# air_flow.net
KiCad netlist of a schematic drawn in EAGLE
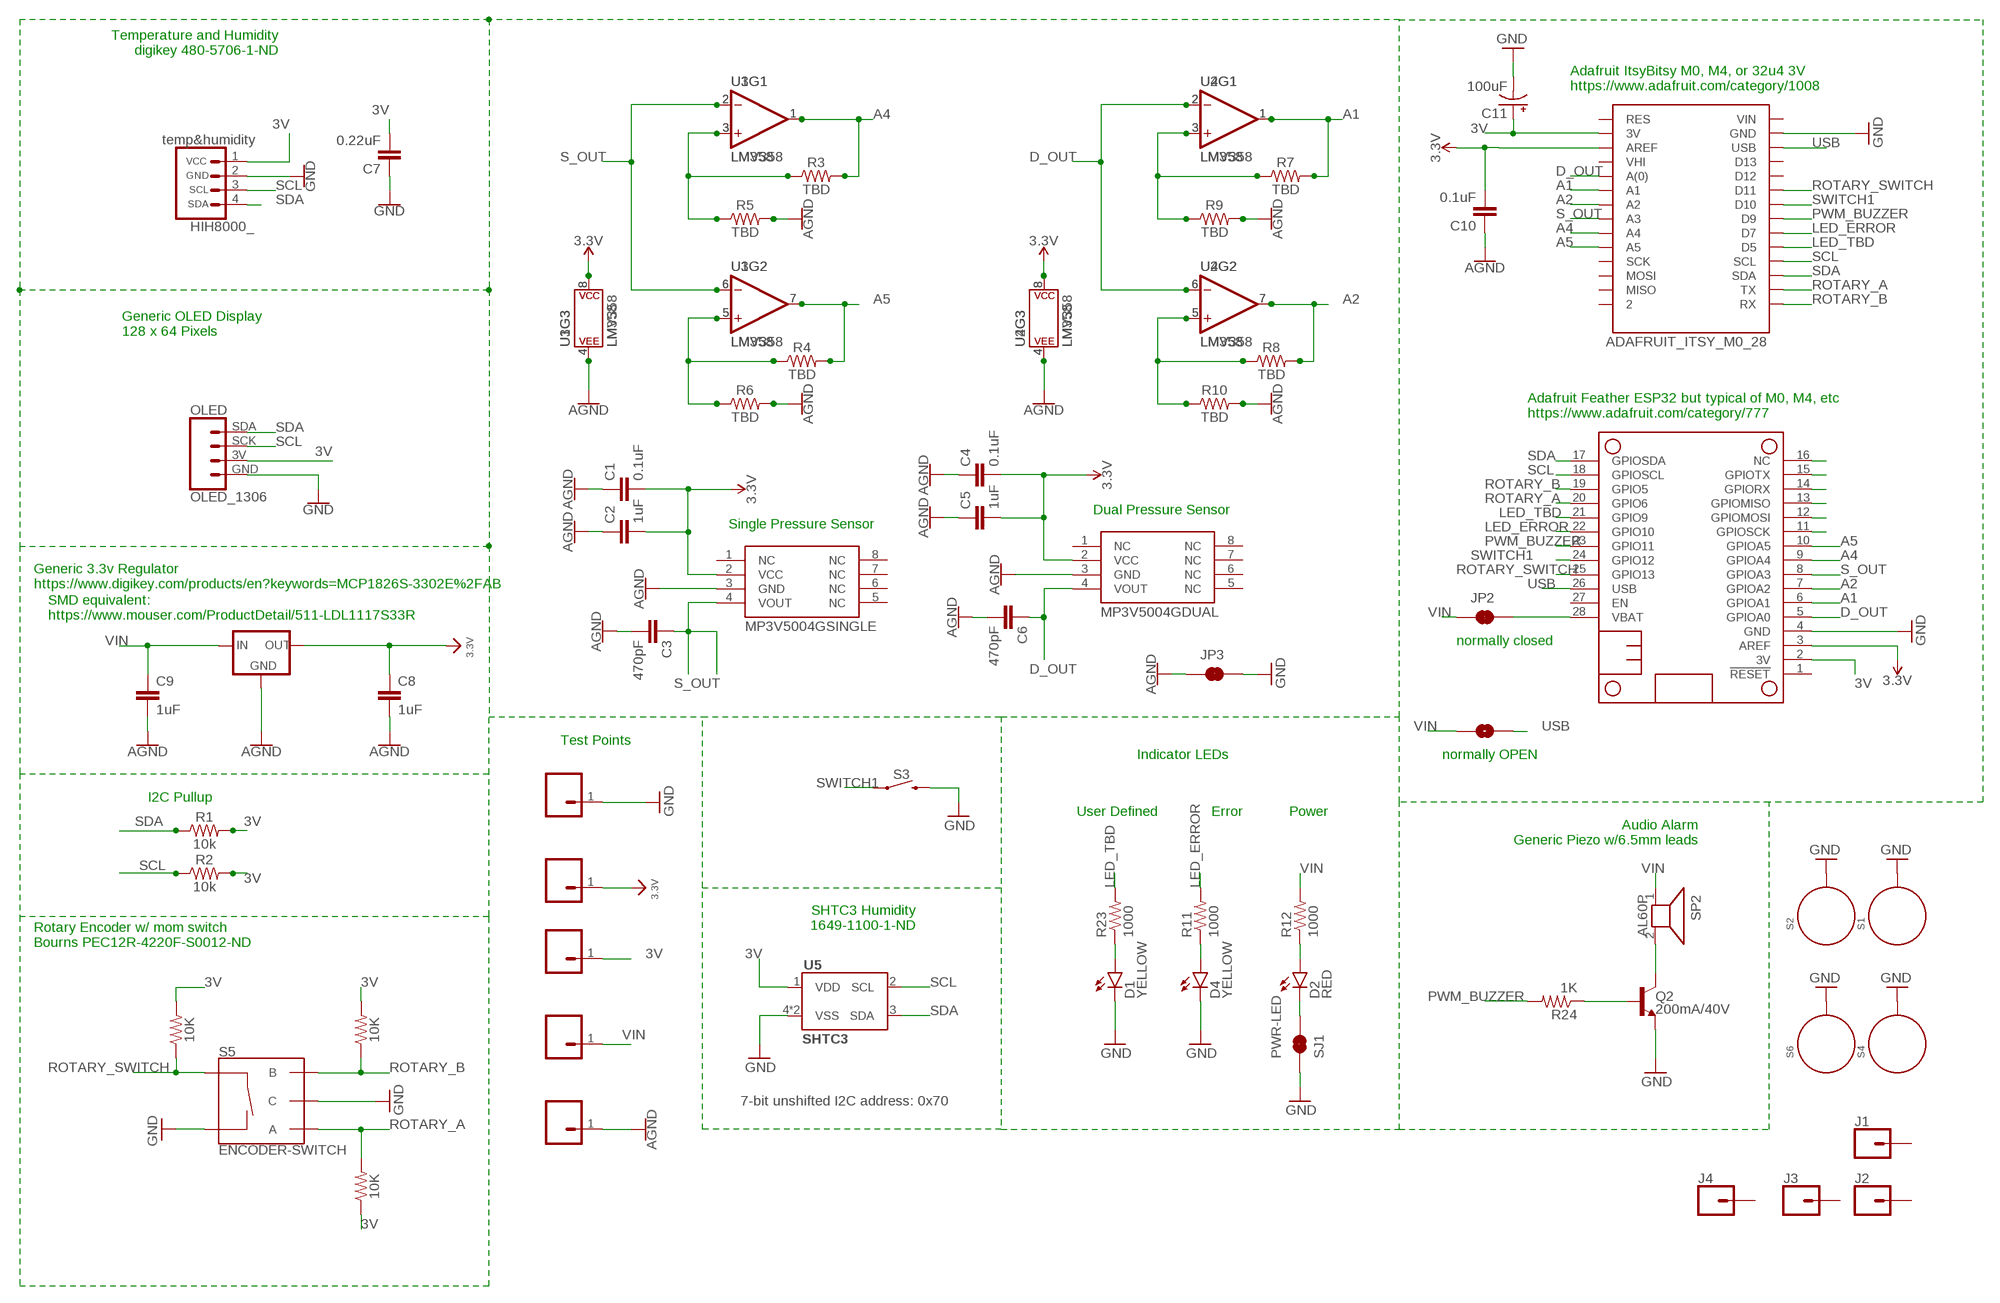
[diagram p0: schematic, sheet 1]

(export (version "E")
  (design (tool "Eeschema 10.0.6"))
  (components
    (comp (ref "3V_REGULATOR")
      (value "LDL1117_5V_REG")
      (footprint "eagle-import:SOT223")
      (libsource (lib "eagle-import") (part "LDL1117_5V_REG"))
    )
    (comp (ref "C1")
      (value "0.1uF")
      (footprint "eagle-import:CAP-PTH-SMALL-KIT")
      (libsource (lib "eagle-import") (part "0.1UF-KIT-EZ-50V-20%"))
    )
    (comp (ref "C2")
      (value "1uF")
      (footprint "eagle-import:CAP-PTH-SMALL-KIT")
      (libsource (lib "eagle-import") (part "0.1UF-KIT-EZ-50V-20%"))
    )
    (comp (ref "C3")
      (value "470pF")
      (footprint "eagle-import:CAP-PTH-SMALL-KIT")
      (libsource (lib "eagle-import") (part "0.1UF-KIT-EZ-50V-20%"))
    )
    (comp (ref "C4")
      (value "0.1uF")
      (footprint "eagle-import:CAP-PTH-SMALL-KIT")
      (libsource (lib "eagle-import") (part "0.1UF-KIT-EZ-50V-20%"))
    )
    (comp (ref "C5")
      (value "1uF")
      (footprint "eagle-import:CAP-PTH-SMALL-KIT")
      (libsource (lib "eagle-import") (part "0.1UF-KIT-EZ-50V-20%"))
    )
    (comp (ref "C6")
      (value "470pF")
      (footprint "eagle-import:CAP-PTH-SMALL-KIT")
      (libsource (lib "eagle-import") (part "0.1UF-KIT-EZ-50V-20%"))
    )
    (comp (ref "C7")
      (value "0.22uF")
      (footprint "eagle-import:CAP-PTH-SMALL-KIT")
      (libsource (lib "eagle-import") (part "0.1UF-KIT-EZ-50V-20%"))
    )
    (comp (ref "C8")
      (value "1uF")
      (footprint "eagle-import:CAP-PTH-SMALL-KIT")
      (libsource (lib "eagle-import") (part "0.1UF-KIT-EZ-50V-20%"))
    )
    (comp (ref "C9")
      (value "1uF")
      (footprint "eagle-import:CAP-PTH-SMALL-KIT")
      (libsource (lib "eagle-import") (part "0.1UF-KIT-EZ-50V-20%"))
    )
    (comp (ref "C10")
      (value "0.1uF")
      (footprint "eagle-import:CAP-PTH-SMALL-KIT")
      (libsource (lib "eagle-import") (part "0.1UF-KIT-EZ-50V-20%"))
    )
    (comp (ref "C11")
      (value "100uF")
      (footprint "eagle-import:CPOL-RADIAL-2.5MM-6.5MM")
      (libsource (lib "eagle-import") (part "100UF-POLAR-RADIAL-2.5MM-25V-20%"))
    )
    (comp (ref "D1")
      (value "YELLOW")
      (footprint "eagle-import:LED-1206")
      (libsource (lib "eagle-import") (part "LED-YELLOWLARGE"))
    )
    (comp (ref "D2")
      (value "RED")
      (footprint "eagle-import:LED-1206")
      (libsource (lib "eagle-import") (part "LED-RED1206"))
    )
    (comp (ref "D4")
      (value "YELLOW")
      (footprint "eagle-import:LED-1206")
      (libsource (lib "eagle-import") (part "LED-YELLOWLARGE"))
    )
    (comp (ref "J1")
      (value "CONN_01")
      (footprint "eagle-import:1X01")
      (libsource (lib "eagle-import") (part "CONN_01"))
    )
    (comp (ref "J2")
      (value "CONN_01")
      (footprint "eagle-import:1X01")
      (libsource (lib "eagle-import") (part "CONN_01"))
    )
    (comp (ref "J3")
      (value "CONN_01")
      (footprint "eagle-import:1X01")
      (libsource (lib "eagle-import") (part "CONN_01"))
    )
    (comp (ref "J4")
      (value "CONN_01")
      (footprint "eagle-import:1X01")
      (libsource (lib "eagle-import") (part "CONN_01"))
    )
    (comp (ref "JP1")
      (value "JUMPER-SMT_2_NO_NO-SILK")
      (footprint "eagle-import:SMT-JUMPER_2_NO_NO-SILK")
      (libsource (lib "eagle-import") (part "JUMPER-SMT_2_NO_NO-SILK"))
    )
    (comp (ref "JP2")
      (value "JUMPER-SMT_2_NC_TRACE_SILK")
      (footprint "eagle-import:SMT-JUMPER_2_NC_TRACE_SILK")
      (libsource (lib "eagle-import") (part "JUMPER-SMT_2_NC_TRACE_SILK"))
    )
    (comp (ref "JP3")
      (value "JUMPER-SMT_2_NC_TRACE_SILK")
      (footprint "eagle-import:SMT-JUMPER_2_NC_TRACE_SILK")
      (libsource (lib "eagle-import") (part "JUMPER-SMT_2_NC_TRACE_SILK"))
    )
    (comp (ref "MS2")
      (value "FEATHERWING_NODIM")
      (footprint "eagle-import:FEATHERWING_DIM")
      (libsource (lib "eagle-import") (part "FEATHERWING_NODIM"))
    )
    (comp (ref "Q2")
      (value "200mA/40V")
      (footprint "eagle-import:TO-92")
      (libsource (lib "eagle-import") (part "TRANS_NPN-2N3904"))
    )
    (comp (ref "R1")
      (value "10k")
      (footprint "eagle-import:AXIAL-0.3")
      (libsource (lib "eagle-import") (part "10KOHM-HORIZ-1/4W-5%"))
    )
    (comp (ref "R2")
      (value "10k")
      (footprint "eagle-import:AXIAL-0.3")
      (libsource (lib "eagle-import") (part "10KOHM-HORIZ-1/4W-5%"))
    )
    (comp (ref "R3")
      (value "TBD")
      (footprint "eagle-import:AXIAL-0.3")
      (libsource (lib "eagle-import") (part "10KOHM-HORIZ-1/4W-5%"))
    )
    (comp (ref "R4")
      (value "TBD")
      (footprint "eagle-import:AXIAL-0.3")
      (libsource (lib "eagle-import") (part "10KOHM-HORIZ-1/4W-5%"))
    )
    (comp (ref "R5")
      (value "TBD")
      (footprint "eagle-import:AXIAL-0.3")
      (libsource (lib "eagle-import") (part "10KOHM-HORIZ-1/4W-5%"))
    )
    (comp (ref "R6")
      (value "TBD")
      (footprint "eagle-import:AXIAL-0.3")
      (libsource (lib "eagle-import") (part "10KOHM-HORIZ-1/4W-5%"))
    )
    (comp (ref "R7")
      (value "TBD")
      (footprint "eagle-import:AXIAL-0.3")
      (libsource (lib "eagle-import") (part "10KOHM-HORIZ-1/4W-5%"))
    )
    (comp (ref "R8")
      (value "TBD")
      (footprint "eagle-import:AXIAL-0.3")
      (libsource (lib "eagle-import") (part "10KOHM-HORIZ-1/4W-5%"))
    )
    (comp (ref "R9")
      (value "TBD")
      (footprint "eagle-import:AXIAL-0.3")
      (libsource (lib "eagle-import") (part "10KOHM-HORIZ-1/4W-5%"))
    )
    (comp (ref "R10")
      (value "TBD")
      (footprint "eagle-import:AXIAL-0.3")
      (libsource (lib "eagle-import") (part "10KOHM-HORIZ-1/4W-5%"))
    )
    (comp (ref "R11")
      (value "1000")
      (footprint "eagle-import:0805")
      (libsource (lib "eagle-import") (part "RESISTOR0805-RES"))
    )
    (comp (ref "R12")
      (value "1000")
      (footprint "eagle-import:0805")
      (libsource (lib "eagle-import") (part "RESISTOR0805-RES"))
    )
    (comp (ref "R13")
      (value "0.3")
      (footprint "eagle-import:0805")
      (libsource (lib "eagle-import") (part "0.3OHM-0805-1/8W-1%"))
    )
    (comp (ref "R14")
      (value "0.3")
      (footprint "eagle-import:0805")
      (libsource (lib "eagle-import") (part "0.3OHM-0805-1/8W-1%"))
    )
    (comp (ref "R15")
      (value "0.3")
      (footprint "eagle-import:0805")
      (libsource (lib "eagle-import") (part "0.3OHM-0805-1/8W-1%"))
    )
    (comp (ref "R16")
      (value "0.3")
      (footprint "eagle-import:0805")
      (libsource (lib "eagle-import") (part "0.3OHM-0805-1/8W-1%"))
    )
    (comp (ref "R17")
      (value "0.3")
      (footprint "eagle-import:0805")
      (libsource (lib "eagle-import") (part "0.3OHM-0805-1/8W-1%"))
    )
    (comp (ref "R18")
      (value "0.3")
      (footprint "eagle-import:0805")
      (libsource (lib "eagle-import") (part "0.3OHM-0805-1/8W-1%"))
    )
    (comp (ref "R19")
      (value "0.3")
      (footprint "eagle-import:0805")
      (libsource (lib "eagle-import") (part "0.3OHM-0805-1/8W-1%"))
    )
    (comp (ref "R20")
      (value "0.3")
      (footprint "eagle-import:0805")
      (libsource (lib "eagle-import") (part "0.3OHM-0805-1/8W-1%"))
    )
    (comp (ref "R21")
      (value "0.3")
      (footprint "eagle-import:0805")
      (libsource (lib "eagle-import") (part "0.3OHM-0805-1/8W-1%"))
    )
    (comp (ref "R22")
      (value "0.3")
      (footprint "eagle-import:0805")
      (libsource (lib "eagle-import") (part "0.3OHM-0805-1/8W-1%"))
    )
    (comp (ref "R23")
      (value "1000")
      (footprint "eagle-import:0805")
      (libsource (lib "eagle-import") (part "RESISTOR0805-RES"))
    )
    (comp (ref "R24")
      (value "1K")
      (footprint "eagle-import:0805")
      (libsource (lib "eagle-import") (part "RESISTOR0805-RES"))
    )
    (comp (ref "R26")
      (value "10K")
      (footprint "eagle-import:0805")
      (libsource (lib "eagle-import") (part "0.3OHM-0805-1/8W-1%"))
    )
    (comp (ref "R27")
      (value "10K")
      (footprint "eagle-import:0805")
      (libsource (lib "eagle-import") (part "0.3OHM-0805-1/8W-1%"))
    )
    (comp (ref "R28")
      (value "10K")
      (footprint "eagle-import:0805")
      (libsource (lib "eagle-import") (part "0.3OHM-0805-1/8W-1%"))
    )
    (comp (ref "S1")
      (value "STANDOFF_ELECTRICAL5-32")
      (footprint "eagle-import:STANDOFF_ELECTRICAL_5_32")
      (libsource (lib "eagle-import") (part "STANDOFF_ELECTRICAL5-32"))
    )
    (comp (ref "S2")
      (value "STANDOFF_ELECTRICAL5-32")
      (footprint "eagle-import:STANDOFF_ELECTRICAL_5_32")
      (libsource (lib "eagle-import") (part "STANDOFF_ELECTRICAL5-32"))
    )
    (comp (ref "S3")
      (value "MOMENTARY-SWITCH-SPST-PTH-6.0MM-KIT")
      (footprint "eagle-import:TACTILE_SWITCH_PTH_6.0MM_KIT")
      (libsource (lib "eagle-import") (part "MOMENTARY-SWITCH-SPST-PTH-6.0MM-KIT"))
    )
    (comp (ref "S4")
      (value "STANDOFF_ELECTRICAL5-32")
      (footprint "eagle-import:STANDOFF_ELECTRICAL_5_32")
      (libsource (lib "eagle-import") (part "STANDOFF_ELECTRICAL5-32"))
    )
    (comp (ref "S5")
      (value "ENCODER-SWITCH")
      (footprint "eagle-import:ROTARY_ENC_PLAIN")
      (libsource (lib "eagle-import") (part "ENCODER-SWITCH"))
    )
    (comp (ref "S6")
      (value "STANDOFF_ELECTRICAL5-32")
      (footprint "eagle-import:STANDOFF_ELECTRICAL_5_32")
      (libsource (lib "eagle-import") (part "STANDOFF_ELECTRICAL5-32"))
    )
    (comp (ref "SJ1")
      (value "PWR-LED")
      (footprint "eagle-import:PAD-JUMPER-2-NC_BY_TRACE_NO_SILK")
      (libsource (lib "eagle-import") (part "JUMPER-PAD-2-NC_BY_TRACENO_SILK"))
    )
    (comp (ref "SP2")
      (value "AL60P")
      (footprint "eagle-import:AL60P")
      (libsource (lib "eagle-import") (part "AL60P"))
    )
    (comp (ref "U$1")
      (value "OLED_1306")
      (footprint "eagle-import:OLED_1306")
      (libsource (lib "eagle-import") (part "OLED_1306"))
    )
    (comp (ref "U$2")
      (value "MP3V5004GSINGLE")
      (footprint "eagle-import:MP3V5004GP")
      (libsource (lib "eagle-import") (part "MP3V5004GSINGLE"))
    )
    (comp (ref "U$3")
      (value "MP3V5004GDUAL")
      (footprint "eagle-import:MP3V5004DP")
      (libsource (lib "eagle-import") (part "MP3V5004GDUAL"))
    )
    (comp (ref "U$4")
      (value "HIH8000_")
      (footprint "eagle-import:HIH8120_TH")
      (libsource (lib "eagle-import") (part "HIH8000_"))
    )
    (comp (ref "U$20")
      (value "CONN_0138MILL")
      (footprint "eagle-import:1X01-40MILL")
      (libsource (lib "eagle-import") (part "CONN_0138MILL"))
    )
    (comp (ref "U$26")
      (value "CONN_0138MILL")
      (footprint "eagle-import:1X01-40MILL")
      (libsource (lib "eagle-import") (part "CONN_0138MILL"))
    )
    (comp (ref "U$31")
      (value "CONN_0138MILL")
      (footprint "eagle-import:1X01-40MILL")
      (libsource (lib "eagle-import") (part "CONN_0138MILL"))
    )
    (comp (ref "U$39")
      (value "CONN_0138MILL")
      (footprint "eagle-import:1X01-40MILL")
      (libsource (lib "eagle-import") (part "CONN_0138MILL"))
    )
    (comp (ref "U$40")
      (value "CONN_0138MILL")
      (footprint "eagle-import:1X01-40MILL")
      (libsource (lib "eagle-import") (part "CONN_0138MILL"))
    )
    (comp (ref "U$45")
      (value "ADAFRUIT_ITSY_M0_28")
      (footprint "eagle-import:ADAFRUIT_ITS_MO_28")
      (libsource (lib "eagle-import") (part "ADAFRUIT_ITSY_M0_28"))
    )
    (comp (ref "U1")
      (value "LM358")
      (footprint "eagle-import:DIP08")
      (libsource (lib "eagle-import") (part "LM358"))
    )
    (comp (ref "U2")
      (value "LM358")
      (footprint "eagle-import:DIP08")
      (libsource (lib "eagle-import") (part "LM358"))
    )
    (comp (ref "U3")
      (value "LMV358")
      (footprint "eagle-import:SO08")
      (libsource (lib "eagle-import") (part "LMV358SOIC"))
    )
    (comp (ref "U4")
      (value "LMV358")
      (footprint "eagle-import:SO08")
      (libsource (lib "eagle-import") (part "LMV358SOIC"))
    )
    (comp (ref "U5")
      (value "SHTC3")
      (footprint "eagle-import:SHTC3")
      (libsource (lib "eagle-import") (part "SHTC3"))
    )
  )
  (nets
    (net (code "1") (name "/3V") (class "Default")
      (node (ref "C11") (pin "1") (pinfunction "+_1") (pintype "passive"))
      (node (ref "C7") (pin "2") (pinfunction "2_2") (pintype "passive"))
      (node (ref "MS2") (pin "2") (pinfunction "3V_2") (pintype "power_in"))
      (node (ref "R1") (pin "P$2") (pinfunction "2_P$2") (pintype "passive"))
      (node (ref "R2") (pin "P$2") (pinfunction "2_P$2") (pintype "passive"))
      (node (ref "R21") (pin "2") (pinfunction "2_2") (pintype "passive"))
      (node (ref "R22") (pin "2") (pinfunction "2_2") (pintype "passive"))
      (node (ref "R26") (pin "2") (pinfunction "2_2") (pintype "passive"))
      (node (ref "R27") (pin "1") (pinfunction "1_1") (pintype "passive"))
      (node (ref "R28") (pin "2") (pinfunction "2_2") (pintype "passive"))
      (node (ref "U$1") (pin "3V") (pinfunction "VCC_3V") (pintype "power_in"))
      (node (ref "U$20") (pin "1") (pinfunction "1_1") (pintype "passive"))
      (node (ref "U$4") (pin "1") (pinfunction "VCC_1") (pintype "passive"))
      (node (ref "U$45") (pin "3V") (pinfunction "3V_3V") (pintype "bidirectional"))
      (node (ref "U5") (pin "1") (pinfunction "VDD_1") (pintype "bidirectional"))
    )
    (net (code "2") (name "/A1") (class "Default")
      (node (ref "MS2") (pin "6") (pinfunction "GPIOA1_6") (pintype "bidirectional"))
      (node (ref "R17") (pin "2") (pinfunction "2_2") (pintype "passive"))
      (node (ref "R7") (pin "P$2") (pinfunction "2_P$2") (pintype "passive"))
      (node (ref "U$45") (pin "A1") (pinfunction "A1_A1") (pintype "bidirectional"))
      (node (ref "U2") (pin "1") (pinfunction "OUT_1") (pintype "output"))
      (node (ref "U4") (pin "1") (pinfunction "OUT_1") (pintype "output"))
    )
    (net (code "3") (name "/A2") (class "Default")
      (node (ref "MS2") (pin "7") (pinfunction "GPIOA2_7") (pintype "bidirectional"))
      (node (ref "R19") (pin "2") (pinfunction "2_2") (pintype "passive"))
      (node (ref "R8") (pin "P$2") (pinfunction "2_P$2") (pintype "passive"))
      (node (ref "U$45") (pin "A2") (pinfunction "A2_A2") (pintype "bidirectional"))
      (node (ref "U2") (pin "7") (pinfunction "OUT_7") (pintype "output"))
      (node (ref "U4") (pin "7") (pinfunction "OUT_7") (pintype "output"))
    )
    (net (code "4") (name "/A4") (class "Default")
      (node (ref "MS2") (pin "9") (pinfunction "GPIOA4_9") (pintype "bidirectional"))
      (node (ref "R16") (pin "2") (pinfunction "2_2") (pintype "passive"))
      (node (ref "R3") (pin "P$2") (pinfunction "2_P$2") (pintype "passive"))
      (node (ref "U$45") (pin "A4") (pinfunction "A4_A4") (pintype "bidirectional"))
      (node (ref "U1") (pin "1") (pinfunction "OUT_1") (pintype "output"))
      (node (ref "U3") (pin "1") (pinfunction "OUT_1") (pintype "output"))
    )
    (net (code "5") (name "/A5") (class "Default")
      (node (ref "MS2") (pin "10") (pinfunction "GPIOA5_10") (pintype "bidirectional"))
      (node (ref "R14") (pin "2") (pinfunction "2_2") (pintype "passive"))
      (node (ref "R4") (pin "P$2") (pinfunction "2_P$2") (pintype "passive"))
      (node (ref "U$45") (pin "A5") (pinfunction "A5_A5") (pintype "bidirectional"))
      (node (ref "U1") (pin "7") (pinfunction "OUT_7") (pintype "output"))
      (node (ref "U3") (pin "7") (pinfunction "OUT_7") (pintype "output"))
    )
    (net (code "6") (name "/D_OUT") (class "Default")
      (node (ref "C6") (pin "1") (pinfunction "1_1") (pintype "passive"))
      (node (ref "MS2") (pin "5") (pinfunction "GPIOA0_5") (pintype "bidirectional"))
      (node (ref "U$3") (pin "4") (pinfunction "VOUT_4") (pintype "bidirectional"))
      (node (ref "U$45") (pin "A0") (pinfunction "A(0)_A0") (pintype "bidirectional"))
      (node (ref "U2") (pin "2") (pinfunction "-IN_2") (pintype "input"))
      (node (ref "U2") (pin "6") (pinfunction "-IN_6") (pintype "input"))
      (node (ref "U4") (pin "2") (pinfunction "-IN_2") (pintype "input"))
      (node (ref "U4") (pin "6") (pinfunction "-IN_6") (pintype "input"))
    )
    (net (code "7") (name "/LED_ERROR") (class "Default")
      (node (ref "MS2") (pin "22") (pinfunction "GPIO10_22") (pintype "bidirectional"))
      (node (ref "R11") (pin "2") (pinfunction "2_2") (pintype "passive"))
      (node (ref "U$45") (pin "D7") (pinfunction "D7_D7") (pintype "bidirectional"))
    )
    (net (code "8") (name "/LED_TBD") (class "Default")
      (node (ref "MS2") (pin "21") (pinfunction "GPIO9_21") (pintype "bidirectional"))
      (node (ref "R23") (pin "2") (pinfunction "2_2") (pintype "passive"))
      (node (ref "U$45") (pin "D5") (pinfunction "D5_D5") (pintype "bidirectional"))
    )
    (net (code "9") (name "/PWM_BUZZER") (class "Default")
      (node (ref "MS2") (pin "23") (pinfunction "GPIO11_23") (pintype "bidirectional"))
      (node (ref "R24") (pin "2") (pinfunction "2_2") (pintype "passive"))
      (node (ref "U$45") (pin "D9") (pinfunction "D9_D9") (pintype "bidirectional"))
    )
    (net (code "10") (name "/ROTARY_A") (class "Default")
      (node (ref "MS2") (pin "20") (pinfunction "GPIO6_20") (pintype "bidirectional"))
      (node (ref "R27") (pin "2") (pinfunction "2_2") (pintype "passive"))
      (node (ref "S5") (pin "A") (pinfunction "A_A") (pintype "bidirectional"))
      (node (ref "U$45") (pin "TX") (pinfunction "TX_TX") (pintype "bidirectional"))
    )
    (net (code "11") (name "/ROTARY_B") (class "Default")
      (node (ref "MS2") (pin "19") (pinfunction "GPIO5_19") (pintype "bidirectional"))
      (node (ref "R26") (pin "1") (pinfunction "1_1") (pintype "passive"))
      (node (ref "S5") (pin "B") (pinfunction "B_B") (pintype "bidirectional"))
      (node (ref "U$45") (pin "RX") (pinfunction "RX_RX") (pintype "bidirectional"))
    )
    (net (code "12") (name "/ROTARY_SWITCH") (class "Default")
      (node (ref "MS2") (pin "25") (pinfunction "GPIO13_25") (pintype "bidirectional"))
      (node (ref "R28") (pin "1") (pinfunction "1_1") (pintype "passive"))
      (node (ref "S5") (pin "SW+") (pinfunction "SW+_SW+") (pintype "bidirectional"))
      (node (ref "U$45") (pin "D11") (pinfunction "D11_D11") (pintype "bidirectional"))
    )
    (net (code "13") (name "/SCL") (class "Default")
      (node (ref "MS2") (pin "18") (pinfunction "GPIOSCL_18") (pintype "bidirectional"))
      (node (ref "R2") (pin "P$1") (pinfunction "1_P$1") (pintype "passive"))
      (node (ref "R22") (pin "1") (pinfunction "1_1") (pintype "passive"))
      (node (ref "U$1") (pin "SCK") (pinfunction "SCK_SCK") (pintype "passive"))
      (node (ref "U$4") (pin "3") (pinfunction "SCL_3") (pintype "power_in"))
      (node (ref "U$45") (pin "SCL") (pinfunction "SCL_SCL") (pintype "bidirectional"))
      (node (ref "U5") (pin "2") (pinfunction "SCL_2") (pintype "bidirectional"))
    )
    (net (code "14") (name "/SDA") (class "Default")
      (node (ref "MS2") (pin "17") (pinfunction "GPIOSDA_17") (pintype "bidirectional"))
      (node (ref "R1") (pin "P$1") (pinfunction "1_P$1") (pintype "passive"))
      (node (ref "R21") (pin "1") (pinfunction "1_1") (pintype "passive"))
      (node (ref "U$1") (pin "SDA") (pinfunction "SDA_SDA") (pintype "passive"))
      (node (ref "U$4") (pin "4") (pinfunction "SDA_4") (pintype "passive"))
      (node (ref "U$45") (pin "SDA") (pinfunction "SDA_SDA") (pintype "bidirectional"))
      (node (ref "U5") (pin "3") (pinfunction "SDA_3") (pintype "bidirectional"))
    )
    (net (code "15") (name "/SWITCH1") (class "Default")
      (node (ref "MS2") (pin "24") (pinfunction "GPIO12_24") (pintype "bidirectional"))
      (node (ref "S3") (pin "1") (pinfunction "1_1") (pintype "passive"))
      (node (ref "U$45") (pin "D10") (pinfunction "D10_D10") (pintype "bidirectional"))
    )
    (net (code "16") (name "/S_OUT") (class "Default")
      (node (ref "C3") (pin "1") (pinfunction "1_1") (pintype "passive"))
      (node (ref "MS2") (pin "8") (pinfunction "GPIOA3_8") (pintype "bidirectional"))
      (node (ref "U$2") (pin "4") (pinfunction "VOUT_4") (pintype "bidirectional"))
      (node (ref "U$45") (pin "A3") (pinfunction "A3_A3") (pintype "bidirectional"))
      (node (ref "U1") (pin "2") (pinfunction "-IN_2") (pintype "input"))
      (node (ref "U1") (pin "6") (pinfunction "-IN_6") (pintype "input"))
      (node (ref "U3") (pin "2") (pinfunction "-IN_2") (pintype "input"))
      (node (ref "U3") (pin "6") (pinfunction "-IN_6") (pintype "input"))
    )
    (net (code "17") (name "/USB") (class "Default")
      (node (ref "JP1") (pin "2") (pinfunction "2_2") (pintype "passive"))
      (node (ref "MS2") (pin "26") (pinfunction "USB_26") (pintype "power_in"))
      (node (ref "U$45") (pin "USB") (pinfunction "USB_USB") (pintype "bidirectional"))
    )
    (net (code "18") (name "/VIN") (class "Default")
      (node (ref "3V_REGULATOR") (pin "3") (pinfunction "IN_3") (pintype "input"))
      (node (ref "C9") (pin "1") (pinfunction "1_1") (pintype "passive"))
      (node (ref "JP1") (pin "1") (pinfunction "1_1") (pintype "passive"))
      (node (ref "JP2") (pin "1") (pinfunction "1_1") (pintype "passive"))
      (node (ref "R12") (pin "2") (pinfunction "2_2") (pintype "passive"))
      (node (ref "SP2") (pin "1") (pinfunction "1_1") (pintype "passive"))
      (node (ref "U$40") (pin "1") (pinfunction "1_1") (pintype "passive"))
    )
    (net (code "19") (name "3.3V") (class "Default")
      (node (ref "3V_REGULATOR") (pin "2") (pinfunction "OUT_2") (pintype "passive"))
      (node (ref "3V_REGULATOR") (pin "4") (pinfunction "OUT_4") (pintype "passive"))
      (node (ref "C1") (pin "2") (pinfunction "2_2") (pintype "passive"))
      (node (ref "C10") (pin "2") (pinfunction "2_2") (pintype "passive"))
      (node (ref "C2") (pin "2") (pinfunction "2_2") (pintype "passive"))
      (node (ref "C4") (pin "2") (pinfunction "2_2") (pintype "passive"))
      (node (ref "C5") (pin "2") (pinfunction "2_2") (pintype "passive"))
      (node (ref "C8") (pin "1") (pinfunction "1_1") (pintype "passive"))
      (node (ref "MS2") (pin "3") (pinfunction "AREF_3") (pintype "passive"))
      (node (ref "U$2") (pin "2") (pinfunction "VCC_2") (pintype "bidirectional"))
      (node (ref "U$3") (pin "2") (pinfunction "VCC_2") (pintype "bidirectional"))
      (node (ref "U$39") (pin "1") (pinfunction "1_1") (pintype "passive"))
      (node (ref "U$45") (pin "AREF") (pinfunction "AREF_AREF") (pintype "bidirectional"))
      (node (ref "U1") (pin "8") (pinfunction "P$V+_8") (pintype "bidirectional"))
      (node (ref "U2") (pin "8") (pinfunction "P$V+_8") (pintype "bidirectional"))
      (node (ref "U3") (pin "8") (pinfunction "P$V+_8") (pintype "bidirectional"))
      (node (ref "U4") (pin "8") (pinfunction "P$V+_8") (pintype "bidirectional"))
    )
    (net (code "20") (name "AGND") (class "Default")
      (node (ref "3V_REGULATOR") (pin "1") (pinfunction "GND_1") (pintype "input"))
      (node (ref "C1") (pin "1") (pinfunction "1_1") (pintype "passive"))
      (node (ref "C10") (pin "1") (pinfunction "1_1") (pintype "passive"))
      (node (ref "C2") (pin "1") (pinfunction "1_1") (pintype "passive"))
      (node (ref "C3") (pin "2") (pinfunction "2_2") (pintype "passive"))
      (node (ref "C4") (pin "1") (pinfunction "1_1") (pintype "passive"))
      (node (ref "C5") (pin "1") (pinfunction "1_1") (pintype "passive"))
      (node (ref "C6") (pin "2") (pinfunction "2_2") (pintype "passive"))
      (node (ref "C8") (pin "2") (pinfunction "2_2") (pintype "passive"))
      (node (ref "C9") (pin "2") (pinfunction "2_2") (pintype "passive"))
      (node (ref "JP3") (pin "1") (pinfunction "1_1") (pintype "passive"))
      (node (ref "R10") (pin "P$2") (pinfunction "2_P$2") (pintype "passive"))
      (node (ref "R13") (pin "2") (pinfunction "2_2") (pintype "passive"))
      (node (ref "R15") (pin "2") (pinfunction "2_2") (pintype "passive"))
      (node (ref "R18") (pin "2") (pinfunction "2_2") (pintype "passive"))
      (node (ref "R20") (pin "2") (pinfunction "2_2") (pintype "passive"))
      (node (ref "R5") (pin "P$2") (pinfunction "2_P$2") (pintype "passive"))
      (node (ref "R6") (pin "P$2") (pinfunction "2_P$2") (pintype "passive"))
      (node (ref "R9") (pin "P$2") (pinfunction "2_P$2") (pintype "passive"))
      (node (ref "U$2") (pin "3") (pinfunction "GND_3") (pintype "bidirectional"))
      (node (ref "U$26") (pin "1") (pinfunction "1_1") (pintype "passive"))
      (node (ref "U$3") (pin "3") (pinfunction "GND_3") (pintype "bidirectional"))
      (node (ref "U1") (pin "4") (pinfunction "P$V-_4") (pintype "bidirectional"))
      (node (ref "U2") (pin "4") (pinfunction "P$V-_4") (pintype "bidirectional"))
      (node (ref "U3") (pin "4") (pinfunction "P$V-_4") (pintype "bidirectional"))
      (node (ref "U4") (pin "4") (pinfunction "P$V-_4") (pintype "bidirectional"))
    )
    (net (code "21") (name "GND") (class "Default")
      (node (ref "C11") (pin "2") (pinfunction "-_2") (pintype "passive"))
      (node (ref "C7") (pin "1") (pinfunction "1_1") (pintype "passive"))
      (node (ref "D1") (pin "C") (pinfunction "C_C") (pintype "passive"))
      (node (ref "D4") (pin "C") (pinfunction "C_C") (pintype "passive"))
      (node (ref "JP3") (pin "2") (pinfunction "2_2") (pintype "passive"))
      (node (ref "MS2") (pin "4") (pinfunction "GND_4") (pintype "power_in"))
      (node (ref "Q2") (pin "1") (pinfunction "E_1") (pintype "passive"))
      (node (ref "S1") (pin "P1") (pinfunction "P$1_P1") (pintype "bidirectional"))
      (node (ref "S2") (pin "P1") (pinfunction "P$1_P1") (pintype "bidirectional"))
      (node (ref "S3") (pin "3") (pinfunction "2_3") (pintype "passive"))
      (node (ref "S4") (pin "P1") (pinfunction "P$1_P1") (pintype "bidirectional"))
      (node (ref "S5") (pin "C") (pinfunction "C_C") (pintype "bidirectional"))
      (node (ref "S5") (pin "SW-") (pinfunction "SW-_SW-") (pintype "bidirectional"))
      (node (ref "S6") (pin "P1") (pinfunction "P$1_P1") (pintype "bidirectional"))
      (node (ref "SJ1") (pin "1") (pinfunction "1_1") (pintype "passive"))
      (node (ref "U$1") (pin "GND") (pinfunction "GND_GND") (pintype "passive"))
      (node (ref "U$31") (pin "1") (pinfunction "1_1") (pintype "passive"))
      (node (ref "U$4") (pin "2") (pinfunction "GND_2") (pintype "passive"))
      (node (ref "U$45") (pin "GND") (pinfunction "GND_GND") (pintype "bidirectional"))
      (node (ref "U5") (pin "4") (pinfunction "VSS_4") (pintype "bidirectional"))
      (node (ref "U5") (pin "5") (pinfunction "VSS_5") (pintype "bidirectional"))
    )
    (net (code "22") (name "Net-(D1-PadA)") (class "Default")
      (node (ref "D1") (pin "A") (pinfunction "A_A") (pintype "passive"))
      (node (ref "R23") (pin "1") (pinfunction "1_1") (pintype "passive"))
    )
    (net (code "23") (name "Net-(D2-PadA)") (class "Default")
      (node (ref "D2") (pin "A") (pinfunction "A_A") (pintype "passive"))
      (node (ref "R12") (pin "1") (pinfunction "1_1") (pintype "passive"))
    )
    (net (code "24") (name "Net-(D2-PadC)") (class "Default")
      (node (ref "D2") (pin "C") (pinfunction "C_C") (pintype "passive"))
      (node (ref "SJ1") (pin "2") (pinfunction "2_2") (pintype "passive"))
    )
    (net (code "25") (name "Net-(D4-PadA)") (class "Default")
      (node (ref "D4") (pin "A") (pinfunction "A_A") (pintype "passive"))
      (node (ref "R11") (pin "1") (pinfunction "1_1") (pintype "passive"))
    )
    (net (code "26") (name "Net-(MS2-VBAT)") (class "Default")
      (node (ref "JP2") (pin "2") (pinfunction "2_2") (pintype "passive"))
      (node (ref "MS2") (pin "28") (pinfunction "VBAT_28") (pintype "power_in"))
    )
    (net (code "27") (name "Net-(Q2-B)") (class "Default")
      (node (ref "Q2") (pin "2") (pinfunction "B_2") (pintype "passive"))
      (node (ref "R24") (pin "1") (pinfunction "1_1") (pintype "passive"))
    )
    (net (code "28") (name "Net-(Q2-C)") (class "Default")
      (node (ref "Q2") (pin "3") (pinfunction "C_3") (pintype "passive"))
      (node (ref "SP2") (pin "2") (pinfunction "2_2") (pintype "passive"))
    )
    (net (code "29") (name "Net-(R3-1)") (class "Default")
      (node (ref "R13") (pin "1") (pinfunction "1_1") (pintype "passive"))
      (node (ref "R16") (pin "1") (pinfunction "1_1") (pintype "passive"))
      (node (ref "R3") (pin "P$1") (pinfunction "1_P$1") (pintype "passive"))
      (node (ref "R5") (pin "P$1") (pinfunction "1_P$1") (pintype "passive"))
      (node (ref "U1") (pin "3") (pinfunction "+IN_3") (pintype "input"))
      (node (ref "U3") (pin "3") (pinfunction "+IN_3") (pintype "input"))
    )
    (net (code "30") (name "Net-(R4-1)") (class "Default")
      (node (ref "R14") (pin "1") (pinfunction "1_1") (pintype "passive"))
      (node (ref "R15") (pin "1") (pinfunction "1_1") (pintype "passive"))
      (node (ref "R4") (pin "P$1") (pinfunction "1_P$1") (pintype "passive"))
      (node (ref "R6") (pin "P$1") (pinfunction "1_P$1") (pintype "passive"))
      (node (ref "U1") (pin "5") (pinfunction "+IN_5") (pintype "input"))
      (node (ref "U3") (pin "5") (pinfunction "+IN_5") (pintype "input"))
    )
    (net (code "31") (name "Net-(R7-1)") (class "Default")
      (node (ref "R17") (pin "1") (pinfunction "1_1") (pintype "passive"))
      (node (ref "R18") (pin "1") (pinfunction "1_1") (pintype "passive"))
      (node (ref "R7") (pin "P$1") (pinfunction "1_P$1") (pintype "passive"))
      (node (ref "R9") (pin "P$1") (pinfunction "1_P$1") (pintype "passive"))
      (node (ref "U2") (pin "3") (pinfunction "+IN_3") (pintype "input"))
      (node (ref "U4") (pin "3") (pinfunction "+IN_3") (pintype "input"))
    )
    (net (code "32") (name "Net-(R10-1)") (class "Default")
      (node (ref "R10") (pin "P$1") (pinfunction "1_P$1") (pintype "passive"))
      (node (ref "R19") (pin "1") (pinfunction "1_1") (pintype "passive"))
      (node (ref "R20") (pin "1") (pinfunction "1_1") (pintype "passive"))
      (node (ref "R8") (pin "P$1") (pinfunction "1_P$1") (pintype "passive"))
      (node (ref "U2") (pin "5") (pinfunction "+IN_5") (pintype "input"))
      (node (ref "U4") (pin "5") (pinfunction "+IN_5") (pintype "input"))
    )
    (net (code "33") (name "unconnected-(J1-Pad1)") (class "Default")
      (node (ref "J1") (pin "1") (pinfunction "1_1") (pintype "passive"))
    )
    (net (code "34") (name "unconnected-(J2-Pad1)") (class "Default")
      (node (ref "J2") (pin "1") (pinfunction "1_1") (pintype "passive"))
    )
    (net (code "35") (name "unconnected-(J3-Pad1)") (class "Default")
      (node (ref "J3") (pin "1") (pinfunction "1_1") (pintype "passive"))
    )
    (net (code "36") (name "unconnected-(J4-Pad1)") (class "Default")
      (node (ref "J4") (pin "1") (pinfunction "1_1") (pintype "passive"))
    )
    (net (code "37") (name "unconnected-(MS2-EN-Pad27)") (class "Default")
      (node (ref "MS2") (pin "27") (pinfunction "EN_27") (pintype "passive"))
    )
    (net (code "38") (name "unconnected-(MS2-GPIOMISO-Pad13)") (class "Default")
      (node (ref "MS2") (pin "13") (pinfunction "GPIOMISO_13") (pintype "bidirectional"))
    )
    (net (code "39") (name "unconnected-(MS2-GPIOMOSI-Pad12)") (class "Default")
      (node (ref "MS2") (pin "12") (pinfunction "GPIOMOSI_12") (pintype "bidirectional"))
    )
    (net (code "40") (name "unconnected-(MS2-GPIORX-Pad14)") (class "Default")
      (node (ref "MS2") (pin "14") (pinfunction "GPIORX_14") (pintype "bidirectional"))
    )
    (net (code "41") (name "unconnected-(MS2-GPIOSCK-Pad11)") (class "Default")
      (node (ref "MS2") (pin "11") (pinfunction "GPIOSCK_11") (pintype "bidirectional"))
    )
    (net (code "42") (name "unconnected-(MS2-GPIOTX-Pad15)") (class "Default")
      (node (ref "MS2") (pin "15") (pinfunction "GPIOTX_15") (pintype "bidirectional"))
    )
    (net (code "43") (name "unconnected-(MS2-NC-Pad16)") (class "Default")
      (node (ref "MS2") (pin "16") (pinfunction "NC_16") (pintype "passive"))
    )
    (net (code "44") (name "unconnected-(MS2-~{RESET}-Pad1)") (class "Default")
      (node (ref "MS2") (pin "1") (pinfunction "~{RESET}_1") (pintype "input"))
    )
    (net (code "45") (name "unconnected-(U$2-NC-Pad1)") (class "Default")
      (node (ref "U$2") (pin "1") (pinfunction "NC_1") (pintype "bidirectional"))
    )
    (net (code "46") (name "unconnected-(U$2-NC-Pad5)") (class "Default")
      (node (ref "U$2") (pin "5") (pinfunction "NC_5") (pintype "bidirectional"))
    )
    (net (code "47") (name "unconnected-(U$2-NC-Pad6)") (class "Default")
      (node (ref "U$2") (pin "6") (pinfunction "NC_6") (pintype "bidirectional"))
    )
    (net (code "48") (name "unconnected-(U$2-NC-Pad7)") (class "Default")
      (node (ref "U$2") (pin "7") (pinfunction "NC_7") (pintype "bidirectional"))
    )
    (net (code "49") (name "unconnected-(U$2-NC-Pad8)") (class "Default")
      (node (ref "U$2") (pin "8") (pinfunction "NC_8") (pintype "bidirectional"))
    )
    (net (code "50") (name "unconnected-(U$3-NC-Pad1)") (class "Default")
      (node (ref "U$3") (pin "1") (pinfunction "NC_1") (pintype "bidirectional"))
    )
    (net (code "51") (name "unconnected-(U$3-NC-Pad5)") (class "Default")
      (node (ref "U$3") (pin "5") (pinfunction "NC_5") (pintype "bidirectional"))
    )
    (net (code "52") (name "unconnected-(U$3-NC-Pad6)") (class "Default")
      (node (ref "U$3") (pin "6") (pinfunction "NC_6") (pintype "bidirectional"))
    )
    (net (code "53") (name "unconnected-(U$3-NC-Pad7)") (class "Default")
      (node (ref "U$3") (pin "7") (pinfunction "NC_7") (pintype "bidirectional"))
    )
    (net (code "54") (name "unconnected-(U$3-NC-Pad8)") (class "Default")
      (node (ref "U$3") (pin "8") (pinfunction "NC_8") (pintype "bidirectional"))
    )
    (net (code "55") (name "unconnected-(U$45-Pad2)") (class "Default")
      (node (ref "U$45") (pin "2") (pinfunction "2_2") (pintype "bidirectional"))
    )
    (net (code "56") (name "unconnected-(U$45-PadD12)") (class "Default")
      (node (ref "U$45") (pin "D12") (pinfunction "D12_D12") (pintype "bidirectional"))
    )
    (net (code "57") (name "unconnected-(U$45-PadD13)") (class "Default")
      (node (ref "U$45") (pin "D13") (pinfunction "D13_D13") (pintype "bidirectional"))
    )
    (net (code "58") (name "unconnected-(U$45-PadMISO)") (class "Default")
      (node (ref "U$45") (pin "MISO") (pinfunction "MISO_MISO") (pintype "bidirectional"))
    )
    (net (code "59") (name "unconnected-(U$45-PadMOSI)") (class "Default")
      (node (ref "U$45") (pin "MOSI") (pinfunction "MOSI_MOSI") (pintype "bidirectional"))
    )
    (net (code "60") (name "unconnected-(U$45-PadRES)") (class "Default")
      (node (ref "U$45") (pin "RES") (pinfunction "RES_RES") (pintype "bidirectional"))
    )
    (net (code "61") (name "unconnected-(U$45-PadSCK)") (class "Default")
      (node (ref "U$45") (pin "SCK") (pinfunction "SCK_SCK") (pintype "bidirectional"))
    )
    (net (code "62") (name "unconnected-(U$45-PadVHI)") (class "Default")
      (node (ref "U$45") (pin "VHI") (pinfunction "VHI_VHI") (pintype "bidirectional"))
    )
    (net (code "63") (name "unconnected-(U$45-PadVIN)") (class "Default")
      (node (ref "U$45") (pin "VIN") (pinfunction "VIN_VIN") (pintype "bidirectional"))
    )
  )
)
